# ardu-shield.net
KiCad netlist of a schematic drawn in Altium Designer
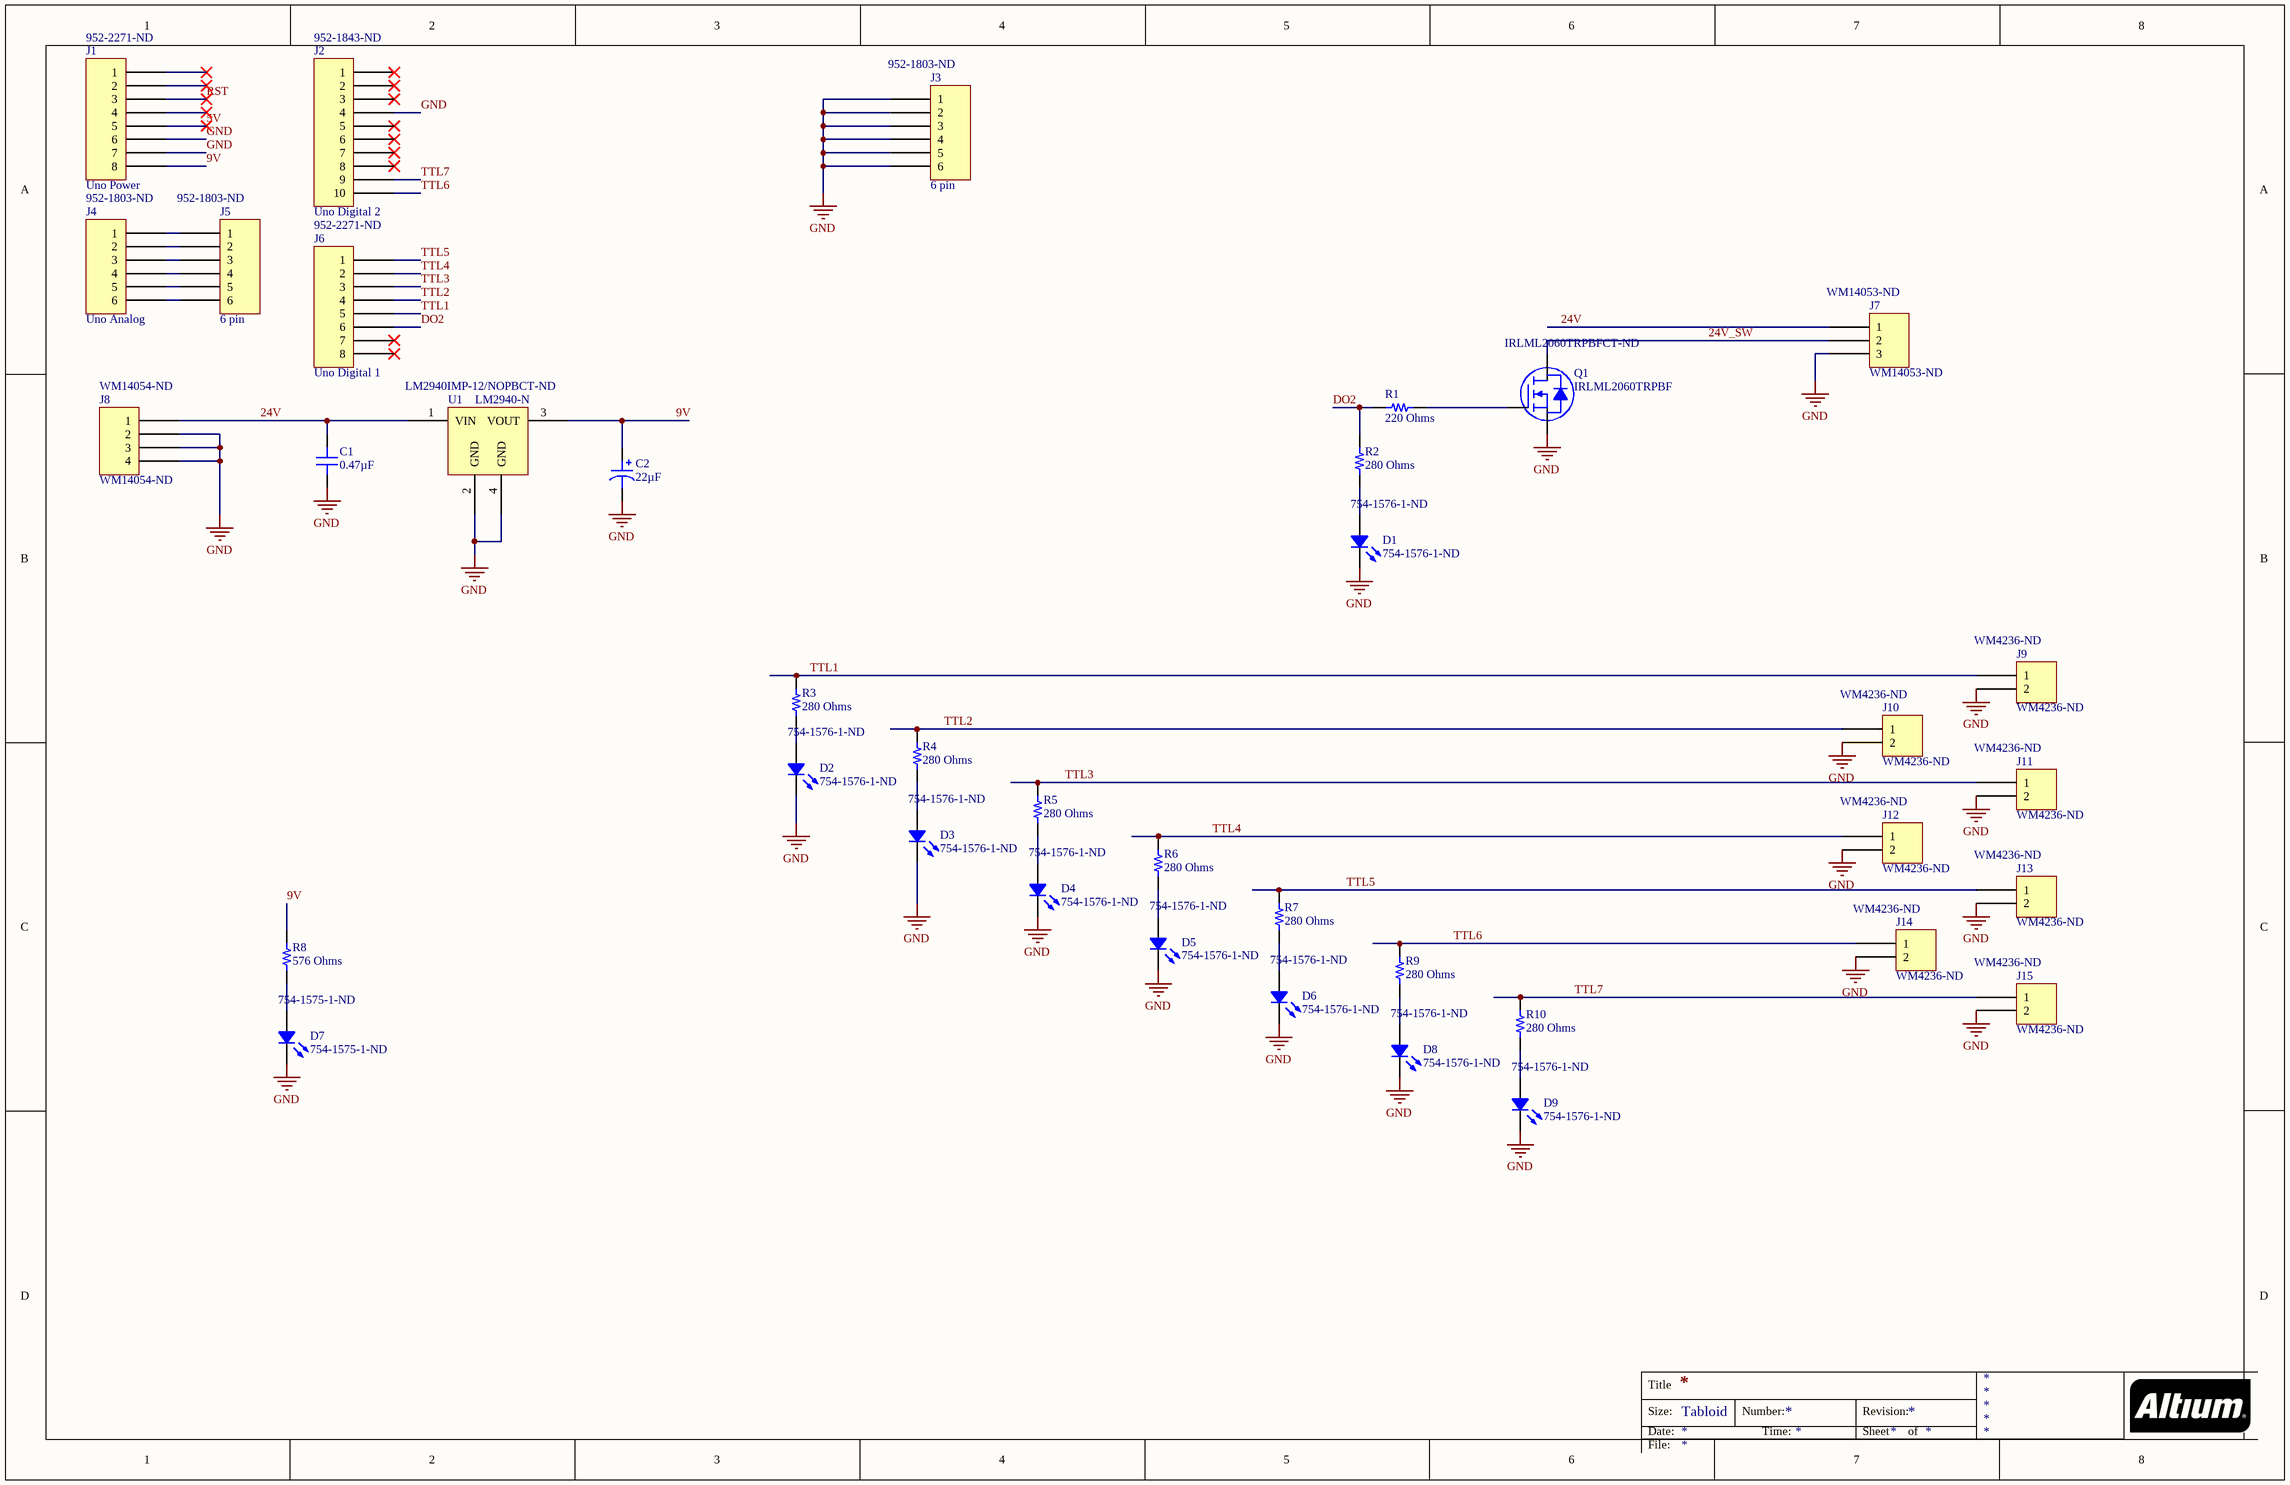
[diagram p0: ardu-shield.SchDoc]

(export (version "E")
  (design (tool "Eeschema 10.0.6"))
  (components
    (comp (ref "C1")
      (value "0.47µF")
      (footprint "CAP 0805_2012")
      (description "CAP CER 0.47UF 50V X7R 0805")
      (fields (field (name "PART NUMBER") "C0805C474K5RACAUTO") (field (name "MANUFACTURER") "KEMET"))
      (libsource (lib "Celestial Altium Library - altium_library") (part "Capacitor"))
    )
    (comp (ref "C2")
      (value "22µF")
      (footprint "CAP POL 2917_7343")
      (description "CAP TANT 22UF 10% 25V 2917")
      (fields (field (name "PART NUMBER") "T491D226K025AT") (field (name "MANUFACTURER") "KEMET"))
      (libsource (lib "Celestial Altium Library - altium_library") (part "Polarised Capacitor"))
    )
    (comp (ref "D1")
      (value "754-1576-1-ND")
      (footprint "APA3010")
      (fields (field (name "SUPPLIER PART NUMBER 1") "754-1576-1-ND"))
      (libsource (lib "kbjs") (part "LED"))
    )
    (comp (ref "D2")
      (value "754-1576-1-ND")
      (footprint "APA3010")
      (fields (field (name "SUPPLIER PART NUMBER 1") "754-1576-1-ND"))
      (libsource (lib "kbjs") (part "LED"))
    )
    (comp (ref "D3")
      (value "754-1576-1-ND")
      (footprint "APA3010")
      (fields (field (name "SUPPLIER PART NUMBER 1") "754-1576-1-ND"))
      (libsource (lib "kbjs") (part "LED"))
    )
    (comp (ref "D4")
      (value "754-1576-1-ND")
      (footprint "APA3010")
      (fields (field (name "SUPPLIER PART NUMBER 1") "754-1576-1-ND"))
      (libsource (lib "kbjs") (part "LED"))
    )
    (comp (ref "D5")
      (value "754-1576-1-ND")
      (footprint "APA3010")
      (fields (field (name "SUPPLIER PART NUMBER 1") "754-1576-1-ND"))
      (libsource (lib "kbjs") (part "LED"))
    )
    (comp (ref "D6")
      (value "754-1576-1-ND")
      (footprint "APA3010")
      (fields (field (name "SUPPLIER PART NUMBER 1") "754-1576-1-ND"))
      (libsource (lib "kbjs") (part "LED"))
    )
    (comp (ref "D7")
      (value "754-1575-1-ND")
      (footprint "APA3010")
      (fields (field (name "SUPPLIER PART NUMBER 1") "754-1575-1-ND"))
      (libsource (lib "kbjs") (part "LED"))
    )
    (comp (ref "D8")
      (value "754-1576-1-ND")
      (footprint "APA3010")
      (fields (field (name "SUPPLIER PART NUMBER 1") "754-1576-1-ND"))
      (libsource (lib "kbjs") (part "LED"))
    )
    (comp (ref "D9")
      (value "754-1576-1-ND")
      (footprint "APA3010")
      (fields (field (name "SUPPLIER PART NUMBER 1") "754-1576-1-ND"))
      (libsource (lib "kbjs") (part "LED"))
    )
    (comp (ref "J1")
      (value "Uno Power")
      (footprint "Pin Header 1x8 TH Pitch 2.54mm")
      (fields (field (name "SUPPLIER PART NUMBER 1") "952-2271-ND"))
      (libsource (lib "kbjs") (part "8 pin"))
    )
    (comp (ref "J2")
      (value "Uno Digital 2")
      (footprint "Pin Header 1x10 TH Pitch 2.54mm")
      (fields (field (name "SUPPLIER PART NUMBER 1") "952-1843-ND"))
      (libsource (lib "kbjs") (part "10 pin"))
    )
    (comp (ref "J3")
      (value "6 pin")
      (footprint "Pin Header 1x6 TH Pitch 2.54mm")
      (fields (field (name "SUPPLIER PART NUMBER 1") "952-1803-ND"))
      (libsource (lib "") (part "6 pin_1"))
    )
    (comp (ref "J4")
      (value "Uno Analog")
      (footprint "Pin Header 1x6 TH Pitch 2.54mm")
      (fields (field (name "SUPPLIER PART NUMBER 1") "952-1803-ND"))
      (libsource (lib "kbjs") (part "6 pin"))
    )
    (comp (ref "J5")
      (value "6 pin")
      (footprint "Pin Header 1x6 TH Pitch 2.54mm")
      (fields (field (name "SUPPLIER PART NUMBER 1") "952-1803-ND"))
      (libsource (lib "") (part "6 pin_1"))
    )
    (comp (ref "J6")
      (value "Uno Digital 1")
      (footprint "Pin Header 1x8 TH Pitch 2.54mm")
      (fields (field (name "SUPPLIER PART NUMBER 1") "952-2271-ND"))
      (libsource (lib "kbjs") (part "8 pin"))
    )
    (comp (ref "J7")
      (value "WM14053-ND")
      (footprint "Molex SL 70551* 3PIN")
      (fields (field (name "SUPPLIER PART NUMBER 1") "WM14053-ND"))
      (libsource (lib "kbjs") (part "3 pin"))
    )
    (comp (ref "J8")
      (value "WM14054-ND")
      (footprint "Molex SL 70551* 4PIN")
      (fields (field (name "SUPPLIER PART NUMBER 1") "WM14054-ND"))
      (libsource (lib "kbjs") (part "4 pin"))
    )
    (comp (ref "J9")
      (value "WM4236-ND")
      (footprint "Molex SL 70551* 2pin")
      (fields (field (name "SUPPLIER PART NUMBER 1") "WM4236-ND"))
      (libsource (lib "kbjs") (part "2 pin"))
    )
    (comp (ref "J10")
      (value "WM4236-ND")
      (footprint "Molex SL 70551* 2pin")
      (fields (field (name "SUPPLIER PART NUMBER 1") "WM4236-ND"))
      (libsource (lib "kbjs") (part "2 pin"))
    )
    (comp (ref "J11")
      (value "WM4236-ND")
      (footprint "Molex SL 70551* 2pin")
      (fields (field (name "SUPPLIER PART NUMBER 1") "WM4236-ND"))
      (libsource (lib "kbjs") (part "2 pin"))
    )
    (comp (ref "J12")
      (value "WM4236-ND")
      (footprint "Molex SL 70551* 2pin")
      (fields (field (name "SUPPLIER PART NUMBER 1") "WM4236-ND"))
      (libsource (lib "kbjs") (part "2 pin"))
    )
    (comp (ref "J13")
      (value "WM4236-ND")
      (footprint "Molex SL 70551* 2pin")
      (fields (field (name "SUPPLIER PART NUMBER 1") "WM4236-ND"))
      (libsource (lib "kbjs") (part "2 pin"))
    )
    (comp (ref "J14")
      (value "WM4236-ND")
      (footprint "Molex SL 70551* 2pin")
      (fields (field (name "SUPPLIER PART NUMBER 1") "WM4236-ND"))
      (libsource (lib "kbjs") (part "2 pin"))
    )
    (comp (ref "J15")
      (value "WM4236-ND")
      (footprint "Molex SL 70551* 2pin")
      (fields (field (name "SUPPLIER PART NUMBER 1") "WM4236-ND"))
      (libsource (lib "kbjs") (part "2 pin"))
    )
    (comp (ref "Q1")
      (value "IRLML2060TRPBF")
      (footprint "INFINEON SOT-23-3")
      (description "MOSFET N-CH 60V 1.2A SOT23-3")
      (fields
        (field (name "MANUFACTURER") "Infineon Technologies")
        (field (name "SUPPLIER PART NUMBER 1") "IRLML2060TRPBFCT-ND")
      )
      (libsource (lib "Celestial Altium Library - altium_library") (part "INFINEON MOSFET N-CH SOT-23-3 GSD"))
    )
    (comp (ref "R1")
      (value "220 Ohms")
      (footprint "RES 0805_2012")
      (description "RES SMD 220 OHM 0.5% 1/10W 0805")
      (fields (field (name "PART NUMBER") "RR1220P-221-D") (field (name "MANUFACTURER") "Susumu"))
      (libsource (lib "Celestial Altium Library - altium_library") (part "Resistor"))
    )
    (comp (ref "R2")
      (value "280 Ohms")
      (footprint "RES 0805_2012")
      (description "RESISTOR")
      (fields
        (field (name "PART NUMBER") "RK73H2ATTD2800F")
        (field (name "MANUFACTURER") "KOA Speer Electronics, Inc.")
      )
      (libsource (lib "Celestial Altium Library - altium_library") (part "Resistor"))
    )
    (comp (ref "R3")
      (value "280 Ohms")
      (footprint "RES 0805_2012")
      (description "RESISTOR")
      (fields
        (field (name "PART NUMBER") "RK73H2ATTD2800F")
        (field (name "MANUFACTURER") "KOA Speer Electronics, Inc.")
      )
      (libsource (lib "Celestial Altium Library - altium_library") (part "Resistor"))
    )
    (comp (ref "R4")
      (value "280 Ohms")
      (footprint "RES 0805_2012")
      (description "RESISTOR")
      (fields
        (field (name "PART NUMBER") "RK73H2ATTD2800F")
        (field (name "MANUFACTURER") "KOA Speer Electronics, Inc.")
      )
      (libsource (lib "Celestial Altium Library - altium_library") (part "Resistor"))
    )
    (comp (ref "R5")
      (value "280 Ohms")
      (footprint "RES 0805_2012")
      (description "RESISTOR")
      (fields
        (field (name "PART NUMBER") "RK73H2ATTD2800F")
        (field (name "MANUFACTURER") "KOA Speer Electronics, Inc.")
      )
      (libsource (lib "Celestial Altium Library - altium_library") (part "Resistor"))
    )
    (comp (ref "R6")
      (value "280 Ohms")
      (footprint "RES 0805_2012")
      (description "RESISTOR")
      (fields
        (field (name "PART NUMBER") "RK73H2ATTD2800F")
        (field (name "MANUFACTURER") "KOA Speer Electronics, Inc.")
      )
      (libsource (lib "Celestial Altium Library - altium_library") (part "Resistor"))
    )
    (comp (ref "R7")
      (value "280 Ohms")
      (footprint "RES 0805_2012")
      (description "RESISTOR")
      (fields
        (field (name "PART NUMBER") "RK73H2ATTD2800F")
        (field (name "MANUFACTURER") "KOA Speer Electronics, Inc.")
      )
      (libsource (lib "Celestial Altium Library - altium_library") (part "Resistor"))
    )
    (comp (ref "R8")
      (value "576 Ohms")
      (footprint "RES 0805_2012")
      (description "RESISTOR")
      (fields
        (field (name "PART NUMBER") "RK73H2ATTD5760F")
        (field (name "MANUFACTURER") "KOA Speer Electronics, Inc.")
      )
      (libsource (lib "Celestial Altium Library - altium_library") (part "Resistor"))
    )
    (comp (ref "R9")
      (value "280 Ohms")
      (footprint "RES 0805_2012")
      (description "RESISTOR")
      (fields
        (field (name "PART NUMBER") "RK73H2ATTD2800F")
        (field (name "MANUFACTURER") "KOA Speer Electronics, Inc.")
      )
      (libsource (lib "Celestial Altium Library - altium_library") (part "Resistor"))
    )
    (comp (ref "R10")
      (value "280 Ohms")
      (footprint "RES 0805_2012")
      (description "RESISTOR")
      (fields
        (field (name "PART NUMBER") "RK73H2ATTD2800F")
        (field (name "MANUFACTURER") "KOA Speer Electronics, Inc.")
      )
      (libsource (lib "Celestial Altium Library - altium_library") (part "Resistor"))
    )
    (comp (ref "U1")
      (value "LM2940-N")
      (footprint "SOT223_M")
      (fields (field (name "SUPPLIER PART NUMBER 1") "LM2940IMP-12/NOPBCT-ND"))
      (libsource (lib "kbjs") (part "LM2940-N"))
    )
  )
  (nets
    (net (code "1") (name "/5V") (class "Default")
      (node (ref "J1") (pin "5") (pinfunction "5_5") (pintype "passive+no_connect"))
    )
    (net (code "2") (name "/9V") (class "Default")
      (node (ref "C2") (pin "1") (pinfunction "1_1") (pintype "passive"))
      (node (ref "J1") (pin "8") (pinfunction "8_8") (pintype "passive"))
      (node (ref "R8") (pin "2") (pinfunction "2_2") (pintype "passive"))
      (node (ref "U1") (pin "3") (pinfunction "VOUT_3") (pintype "passive"))
    )
    (net (code "3") (name "/24V") (class "Default")
      (node (ref "C1") (pin "2") (pinfunction "2_2") (pintype "passive"))
      (node (ref "J7") (pin "1") (pinfunction "1_1") (pintype "passive"))
      (node (ref "J8") (pin "1") (pinfunction "1_1") (pintype "passive"))
      (node (ref "U1") (pin "1") (pinfunction "VIN_1") (pintype "passive"))
    )
    (net (code "4") (name "/24V_SW") (class "Default")
      (node (ref "J7") (pin "2") (pinfunction "2_2") (pintype "passive"))
      (node (ref "Q1") (pin "3") (pinfunction "D_3") (pintype "passive"))
    )
    (net (code "5") (name "/DO2") (class "Default")
      (node (ref "J6") (pin "6") (pinfunction "6_6") (pintype "passive"))
      (node (ref "R1") (pin "1") (pinfunction "1_1") (pintype "passive"))
      (node (ref "R2") (pin "2") (pinfunction "2_2") (pintype "passive"))
    )
    (net (code "6") (name "/RST") (class "Default")
      (node (ref "J1") (pin "3") (pinfunction "3_3") (pintype "passive+no_connect"))
    )
    (net (code "7") (name "/TTL1") (class "Default")
      (node (ref "J6") (pin "5") (pinfunction "5_5") (pintype "passive"))
      (node (ref "J9") (pin "1") (pinfunction "1_1") (pintype "passive"))
      (node (ref "R3") (pin "2") (pinfunction "2_2") (pintype "passive"))
    )
    (net (code "8") (name "/TTL2") (class "Default")
      (node (ref "J10") (pin "1") (pinfunction "1_1") (pintype "passive"))
      (node (ref "J6") (pin "4") (pinfunction "4_4") (pintype "passive"))
      (node (ref "R4") (pin "2") (pinfunction "2_2") (pintype "passive"))
    )
    (net (code "9") (name "/TTL3") (class "Default")
      (node (ref "J11") (pin "1") (pinfunction "1_1") (pintype "passive"))
      (node (ref "J6") (pin "3") (pinfunction "3_3") (pintype "passive"))
      (node (ref "R5") (pin "2") (pinfunction "2_2") (pintype "passive"))
    )
    (net (code "10") (name "/TTL4") (class "Default")
      (node (ref "J12") (pin "1") (pinfunction "1_1") (pintype "passive"))
      (node (ref "J6") (pin "2") (pinfunction "2_2") (pintype "passive"))
      (node (ref "R6") (pin "2") (pinfunction "2_2") (pintype "passive"))
    )
    (net (code "11") (name "/TTL5") (class "Default")
      (node (ref "J13") (pin "1") (pinfunction "1_1") (pintype "passive"))
      (node (ref "J6") (pin "1") (pinfunction "1_1") (pintype "passive"))
      (node (ref "R7") (pin "2") (pinfunction "2_2") (pintype "passive"))
    )
    (net (code "12") (name "/TTL6") (class "Default")
      (node (ref "J14") (pin "1") (pinfunction "1_1") (pintype "passive"))
      (node (ref "J2") (pin "10") (pinfunction "10_10") (pintype "passive"))
      (node (ref "R9") (pin "2") (pinfunction "2_2") (pintype "passive"))
    )
    (net (code "13") (name "/TTL7") (class "Default")
      (node (ref "J15") (pin "1") (pinfunction "1_1") (pintype "passive"))
      (node (ref "J2") (pin "9") (pinfunction "9_9") (pintype "passive"))
      (node (ref "R10") (pin "2") (pinfunction "2_2") (pintype "passive"))
    )
    (net (code "14") (name "GND") (class "Default")
      (node (ref "C1") (pin "1") (pinfunction "1_1") (pintype "passive"))
      (node (ref "C2") (pin "2") (pinfunction "2_2") (pintype "passive"))
      (node (ref "D1") (pin "1") (pinfunction "1_1") (pintype "power_in"))
      (node (ref "D2") (pin "1") (pinfunction "1_1") (pintype "power_in"))
      (node (ref "D3") (pin "1") (pinfunction "1_1") (pintype "power_in"))
      (node (ref "D4") (pin "1") (pinfunction "1_1") (pintype "power_in"))
      (node (ref "D5") (pin "1") (pinfunction "1_1") (pintype "power_in"))
      (node (ref "D6") (pin "1") (pinfunction "1_1") (pintype "power_in"))
      (node (ref "D7") (pin "1") (pinfunction "1_1") (pintype "power_in"))
      (node (ref "D8") (pin "1") (pinfunction "1_1") (pintype "power_in"))
      (node (ref "D9") (pin "1") (pinfunction "1_1") (pintype "power_in"))
      (node (ref "J1") (pin "6") (pinfunction "6_6") (pintype "passive"))
      (node (ref "J1") (pin "7") (pinfunction "7_7") (pintype "passive"))
      (node (ref "J10") (pin "2") (pinfunction "2_2") (pintype "passive"))
      (node (ref "J11") (pin "2") (pinfunction "2_2") (pintype "passive"))
      (node (ref "J12") (pin "2") (pinfunction "2_2") (pintype "passive"))
      (node (ref "J13") (pin "2") (pinfunction "2_2") (pintype "passive"))
      (node (ref "J14") (pin "2") (pinfunction "2_2") (pintype "passive"))
      (node (ref "J15") (pin "2") (pinfunction "2_2") (pintype "passive"))
      (node (ref "J2") (pin "4") (pinfunction "4_4") (pintype "passive"))
      (node (ref "J3") (pin "1") (pinfunction "1_1") (pintype "passive"))
      (node (ref "J3") (pin "2") (pinfunction "2_2") (pintype "passive"))
      (node (ref "J3") (pin "3") (pinfunction "3_3") (pintype "passive"))
      (node (ref "J3") (pin "4") (pinfunction "4_4") (pintype "passive"))
      (node (ref "J3") (pin "5") (pinfunction "5_5") (pintype "passive"))
      (node (ref "J3") (pin "6") (pinfunction "6_6") (pintype "passive"))
      (node (ref "J7") (pin "3") (pinfunction "3_3") (pintype "passive"))
      (node (ref "J8") (pin "2") (pinfunction "2_2") (pintype "passive"))
      (node (ref "J8") (pin "3") (pinfunction "3_3") (pintype "passive"))
      (node (ref "J8") (pin "4") (pinfunction "4_4") (pintype "passive"))
      (node (ref "J9") (pin "2") (pinfunction "2_2") (pintype "passive"))
      (node (ref "Q1") (pin "2") (pinfunction "S_2") (pintype "passive"))
      (node (ref "U1") (pin "2") (pinfunction "GND_2") (pintype "passive"))
      (node (ref "U1") (pin "4") (pinfunction "GND_4") (pintype "passive"))
    )
    (net (code "15") (name "Net-(D1-Pad2)") (class "Default")
      (node (ref "D1") (pin "2") (pinfunction "2_2") (pintype "power_in"))
      (node (ref "R2") (pin "1") (pinfunction "1_1") (pintype "passive"))
    )
    (net (code "16") (name "Net-(D2-Pad2)") (class "Default")
      (node (ref "D2") (pin "2") (pinfunction "2_2") (pintype "power_in"))
      (node (ref "R3") (pin "1") (pinfunction "1_1") (pintype "passive"))
    )
    (net (code "17") (name "Net-(D3-Pad2)") (class "Default")
      (node (ref "D3") (pin "2") (pinfunction "2_2") (pintype "power_in"))
      (node (ref "R4") (pin "1") (pinfunction "1_1") (pintype "passive"))
    )
    (net (code "18") (name "Net-(D4-Pad2)") (class "Default")
      (node (ref "D4") (pin "2") (pinfunction "2_2") (pintype "power_in"))
      (node (ref "R5") (pin "1") (pinfunction "1_1") (pintype "passive"))
    )
    (net (code "19") (name "Net-(D5-Pad2)") (class "Default")
      (node (ref "D5") (pin "2") (pinfunction "2_2") (pintype "power_in"))
      (node (ref "R6") (pin "1") (pinfunction "1_1") (pintype "passive"))
    )
    (net (code "20") (name "Net-(D6-Pad2)") (class "Default")
      (node (ref "D6") (pin "2") (pinfunction "2_2") (pintype "power_in"))
      (node (ref "R7") (pin "1") (pinfunction "1_1") (pintype "passive"))
    )
    (net (code "21") (name "Net-(D7-Pad2)") (class "Default")
      (node (ref "D7") (pin "2") (pinfunction "2_2") (pintype "power_in"))
      (node (ref "R8") (pin "1") (pinfunction "1_1") (pintype "passive"))
    )
    (net (code "22") (name "Net-(D8-Pad2)") (class "Default")
      (node (ref "D8") (pin "2") (pinfunction "2_2") (pintype "power_in"))
      (node (ref "R9") (pin "1") (pinfunction "1_1") (pintype "passive"))
    )
    (net (code "23") (name "Net-(D9-Pad2)") (class "Default")
      (node (ref "D9") (pin "2") (pinfunction "2_2") (pintype "power_in"))
      (node (ref "R10") (pin "1") (pinfunction "1_1") (pintype "passive"))
    )
    (net (code "24") (name "Net-(J4-Pad1)") (class "Default")
      (node (ref "J4") (pin "1") (pinfunction "1_1") (pintype "passive"))
      (node (ref "J5") (pin "1") (pinfunction "1_1") (pintype "passive"))
    )
    (net (code "25") (name "Net-(J4-Pad2)") (class "Default")
      (node (ref "J4") (pin "2") (pinfunction "2_2") (pintype "passive"))
      (node (ref "J5") (pin "2") (pinfunction "2_2") (pintype "passive"))
    )
    (net (code "26") (name "Net-(J4-Pad3)") (class "Default")
      (node (ref "J4") (pin "3") (pinfunction "3_3") (pintype "passive"))
      (node (ref "J5") (pin "3") (pinfunction "3_3") (pintype "passive"))
    )
    (net (code "27") (name "Net-(J4-Pad4)") (class "Default")
      (node (ref "J4") (pin "4") (pinfunction "4_4") (pintype "passive"))
      (node (ref "J5") (pin "4") (pinfunction "4_4") (pintype "passive"))
    )
    (net (code "28") (name "Net-(J4-Pad5)") (class "Default")
      (node (ref "J4") (pin "5") (pinfunction "5_5") (pintype "passive"))
      (node (ref "J5") (pin "5") (pinfunction "5_5") (pintype "passive"))
    )
    (net (code "29") (name "Net-(J4-Pad6)") (class "Default")
      (node (ref "J4") (pin "6") (pinfunction "6_6") (pintype "passive"))
      (node (ref "J5") (pin "6") (pinfunction "6_6") (pintype "passive"))
    )
    (net (code "30") (name "Net-(Q1-G)") (class "Default")
      (node (ref "Q1") (pin "1") (pinfunction "G_1") (pintype "passive"))
      (node (ref "R1") (pin "2") (pinfunction "2_2") (pintype "passive"))
    )
    (net (code "31") (name "unconnected-(J1-Pad1)") (class "Default")
      (node (ref "J1") (pin "1") (pinfunction "1_1") (pintype "passive+no_connect"))
    )
    (net (code "32") (name "unconnected-(J1-Pad2)") (class "Default")
      (node (ref "J1") (pin "2") (pinfunction "2_2") (pintype "passive+no_connect"))
    )
    (net (code "33") (name "unconnected-(J1-Pad4)") (class "Default")
      (node (ref "J1") (pin "4") (pinfunction "4_4") (pintype "passive+no_connect"))
    )
    (net (code "34") (name "unconnected-(J2-Pad1)") (class "Default")
      (node (ref "J2") (pin "1") (pinfunction "1_1") (pintype "passive+no_connect"))
    )
    (net (code "35") (name "unconnected-(J2-Pad2)") (class "Default")
      (node (ref "J2") (pin "2") (pinfunction "2_2") (pintype "passive+no_connect"))
    )
    (net (code "36") (name "unconnected-(J2-Pad3)") (class "Default")
      (node (ref "J2") (pin "3") (pinfunction "3_3") (pintype "passive+no_connect"))
    )
    (net (code "37") (name "unconnected-(J2-Pad5)") (class "Default")
      (node (ref "J2") (pin "5") (pinfunction "5_5") (pintype "passive+no_connect"))
    )
    (net (code "38") (name "unconnected-(J2-Pad6)") (class "Default")
      (node (ref "J2") (pin "6") (pinfunction "6_6") (pintype "passive+no_connect"))
    )
    (net (code "39") (name "unconnected-(J2-Pad7)") (class "Default")
      (node (ref "J2") (pin "7") (pinfunction "7_7") (pintype "passive+no_connect"))
    )
    (net (code "40") (name "unconnected-(J2-Pad8)") (class "Default")
      (node (ref "J2") (pin "8") (pinfunction "8_8") (pintype "passive+no_connect"))
    )
    (net (code "41") (name "unconnected-(J6-Pad7)") (class "Default")
      (node (ref "J6") (pin "7") (pinfunction "7_7") (pintype "passive+no_connect"))
    )
    (net (code "42") (name "unconnected-(J6-Pad8)") (class "Default")
      (node (ref "J6") (pin "8") (pinfunction "8_8") (pintype "passive+no_connect"))
    )
  )
)
